# 07_Audio_SPK.net
KiCad netlist of a schematic drawn in Altium Designer
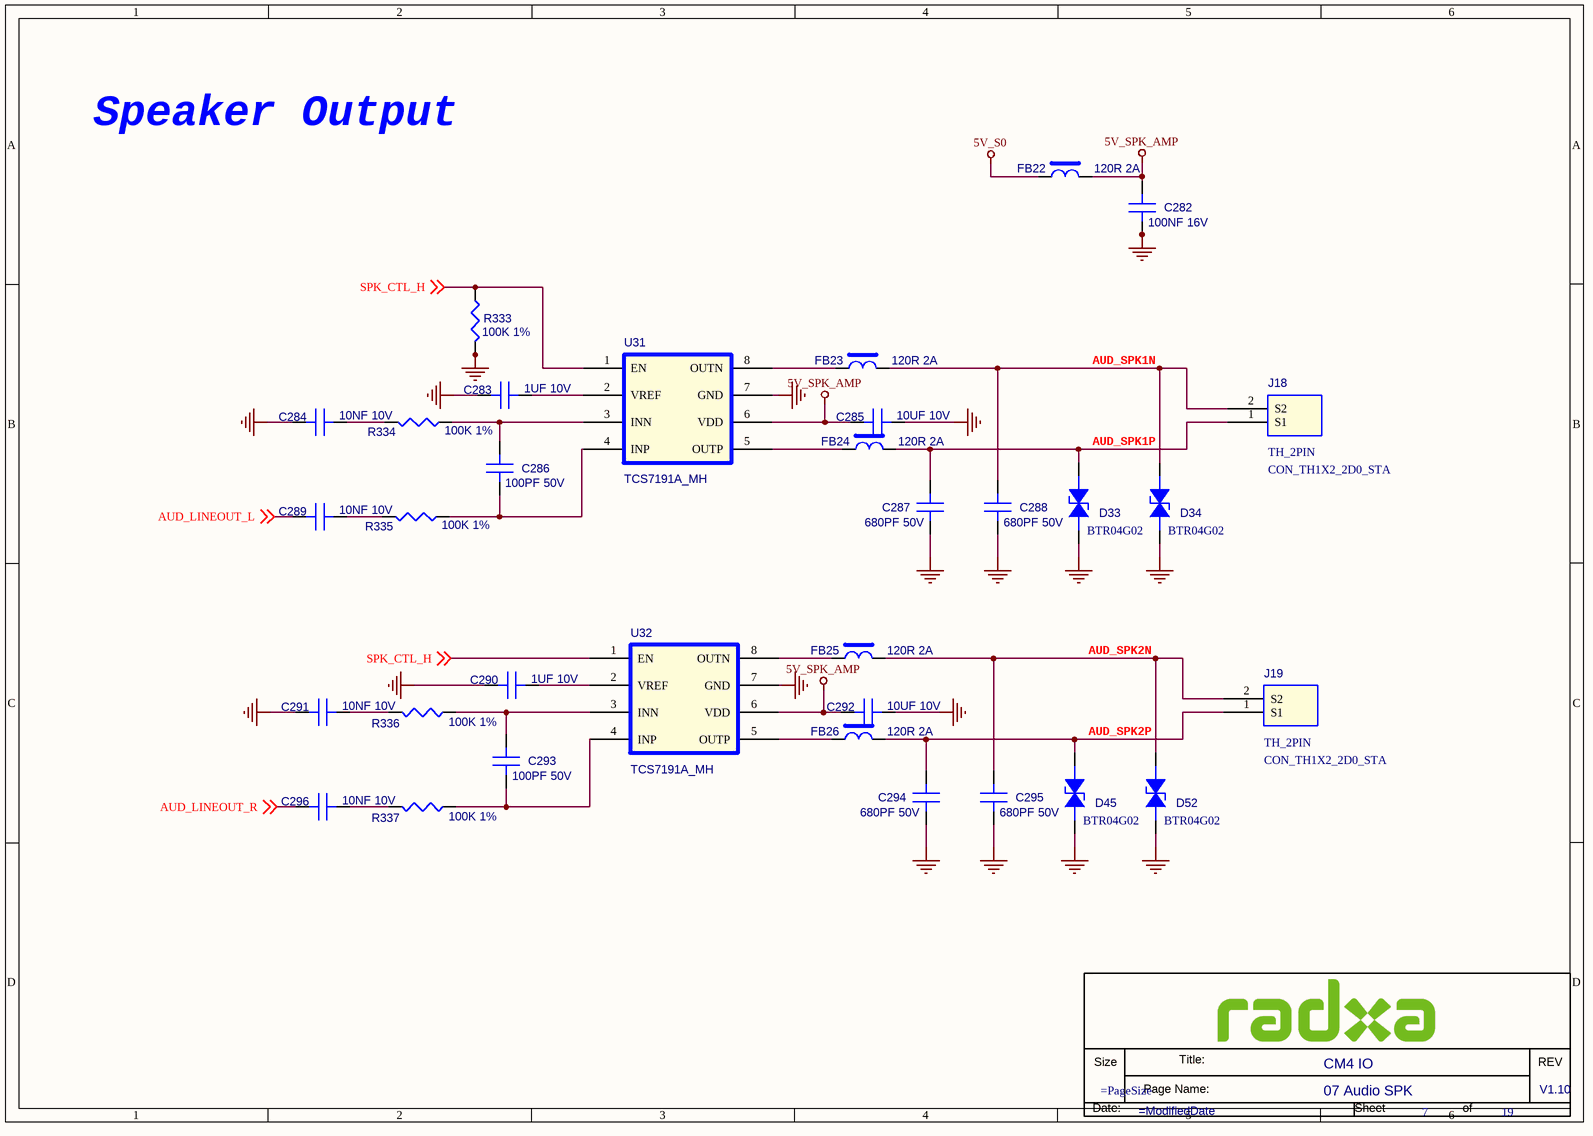
[diagram p0: 07 Audio SPK.SchDoc]

(export (version "E")
  (design (tool "Eeschema 10.0.6"))
  (components
    (comp (ref "C282")
      (value "100NF 16V")
      (footprint "C0201")
      (description "SMD  0201  100NF  16V  X5R  ±20%  ROHS")
      (fields (field (name "PART NUMBER") "A1C01.00099"))
      (libsource (lib "*") (part "C"))
    )
    (comp (ref "C283")
      (value "1UF 10V")
      (footprint "C0201")
      (description "SMD  0201  1UF  10V  X5R  ±20%  ROHS")
      (fields (field (name "PART NUMBER") "A1C01.00081"))
      (libsource (lib "*") (part "C"))
    )
    (comp (ref "C284")
      (value "10NF 10V")
      (footprint "C0201")
      (description "SMD  0201  10NF  10V  X5R  ±20%  ROHS")
      (fields (field (name "PART NUMBER") "A1C01.00095"))
      (libsource (lib "*") (part "C"))
    )
    (comp (ref "C285")
      (value "10UF 10V")
      (footprint "C0603")
      (description "SMD  0603  10UF  10V  X5R  ±20%  ROHS")
      (fields (field (name "PART NUMBER") "A1C01.00075"))
      (libsource (lib "*") (part "C"))
    )
    (comp (ref "C286")
      (value "100PF 50V")
      (footprint "C0201")
      (description "SMD  0201  100PF  50V  NPO  ±5%  ROHS")
      (fields (field (name "PART NUMBER") "A1C01.00382"))
      (libsource (lib "*") (part "C"))
    )
    (comp (ref "C287")
      (value "680PF 50V")
      (footprint "C0201")
      (description "SMD  0201  680PF  50V  X7R  ±10%  ROHS")
      (fields (field (name "PART NUMBER") "A1C01.00071"))
      (libsource (lib "*") (part "C"))
    )
    (comp (ref "C288")
      (value "680PF 50V")
      (footprint "C0201")
      (description "SMD  0201  680PF  50V  X7R  ±10%  ROHS")
      (fields (field (name "PART NUMBER") "A1C01.00071"))
      (libsource (lib "*") (part "C"))
    )
    (comp (ref "C289")
      (value "10NF 10V")
      (footprint "C0201")
      (description "SMD  0201  10NF  10V  X5R  ±20%  ROHS")
      (fields (field (name "PART NUMBER") "A1C01.00095"))
      (libsource (lib "*") (part "C"))
    )
    (comp (ref "C290")
      (value "1UF 10V")
      (footprint "C0201")
      (description "SMD  0201  1UF  10V  X5R  ±20%  ROHS")
      (fields (field (name "PART NUMBER") "A1C01.00081"))
      (libsource (lib "*") (part "C"))
    )
    (comp (ref "C291")
      (value "10NF 10V")
      (footprint "C0201")
      (description "SMD  0201  10NF  10V  X5R  ±20%  ROHS")
      (fields (field (name "PART NUMBER") "A1C01.00095"))
      (libsource (lib "*") (part "C"))
    )
    (comp (ref "C292")
      (value "10UF 10V")
      (footprint "C0603")
      (description "SMD  0603  10UF  10V  X5R  ±20%  ROHS")
      (fields (field (name "PART NUMBER") "A1C01.00075"))
      (libsource (lib "*") (part "C"))
    )
    (comp (ref "C293")
      (value "100PF 50V")
      (footprint "C0201")
      (description "SMD  0201  100PF  50V  NPO  ±5%  ROHS")
      (fields (field (name "PART NUMBER") "A1C01.00382"))
      (libsource (lib "*") (part "C"))
    )
    (comp (ref "C294")
      (value "680PF 50V")
      (footprint "C0201")
      (description "SMD  0201  680PF  50V  X7R  ±10%  ROHS")
      (fields (field (name "PART NUMBER") "A1C01.00071"))
      (libsource (lib "*") (part "C"))
    )
    (comp (ref "C295")
      (value "680PF 50V")
      (footprint "C0201")
      (description "SMD  0201  680PF  50V  X7R  ±10%  ROHS")
      (fields (field (name "PART NUMBER") "A1C01.00071"))
      (libsource (lib "*") (part "C"))
    )
    (comp (ref "C296")
      (value "10NF 10V")
      (footprint "C0201")
      (description "SMD  0201  10NF  10V  X5R  ±20%  ROHS")
      (fields (field (name "PART NUMBER") "A1C01.00095"))
      (libsource (lib "*") (part "C"))
    )
    (comp (ref "D33")
      (value "BTR04G02")
      (footprint "DFN1006-2L")
      (description "SMD  编带  0402  BTR04G02  B-tron  ROHS")
      (fields (field (name "PART NUMBER") "A1D02.00002"))
      (libsource (lib "*") (part "ESD"))
    )
    (comp (ref "D34")
      (value "BTR04G02")
      (footprint "DFN1006-2L")
      (description "SMD  编带  0402  BTR04G02  B-tron  ROHS")
      (fields (field (name "PART NUMBER") "A1D02.00002"))
      (libsource (lib "*") (part "ESD"))
    )
    (comp (ref "D45")
      (value "BTR04G02")
      (footprint "DFN1006-2L")
      (description "SMD  编带  0402  BTR04G02  B-tron  ROHS")
      (fields (field (name "PART NUMBER") "A1D02.00002"))
      (libsource (lib "*") (part "ESD"))
    )
    (comp (ref "D52")
      (value "BTR04G02")
      (footprint "DFN1006-2L")
      (description "SMD  编带  0402  BTR04G02  B-tron  ROHS")
      (fields (field (name "PART NUMBER") "A1D02.00002"))
      (libsource (lib "*") (part "ESD"))
    )
    (comp (ref "FB22")
      (value "120R 2A")
      (footprint "FB0402")
      (description "SMD  0402  FB120R  2A  ±25%  ROHS")
      (fields (field (name "PART NUMBER") "A1L09.00004"))
      (libsource (lib "*") (part "BEAD"))
    )
    (comp (ref "FB23")
      (value "120R 2A")
      (footprint "FB0402")
      (description "SMD  0402  FB120R  2A  ±25%  ROHS")
      (fields (field (name "PART NUMBER") "A1L09.00004"))
      (libsource (lib "*") (part "BEAD"))
    )
    (comp (ref "FB24")
      (value "120R 2A")
      (footprint "FB0402")
      (description "SMD  0402  FB120R  2A  ±25%  ROHS")
      (fields (field (name "PART NUMBER") "A1L09.00004"))
      (libsource (lib "*") (part "BEAD"))
    )
    (comp (ref "FB25")
      (value "120R 2A")
      (footprint "FB0402")
      (description "SMD  0402  FB120R  2A  ±25%  ROHS")
      (fields (field (name "PART NUMBER") "A1L09.00004"))
      (libsource (lib "*") (part "BEAD"))
    )
    (comp (ref "FB26")
      (value "120R 2A")
      (footprint "FB0402")
      (description "SMD  0402  FB120R  2A  ±25%  ROHS")
      (fields (field (name "PART NUMBER") "A1L09.00004"))
      (libsource (lib "*") (part "BEAD"))
    )
    (comp (ref "J18")
      (value "TH_2PIN")
      (footprint "CON_TH1X2_2D54_STA")
      (fields (field (name "PART NUMBER") "A1J02.00089") (field (name "PCB FOOTPRINT") "CON_TH1X2_2D0_STA"))
      (libsource (lib "*") (part "TH_2PIN"))
    )
    (comp (ref "J19")
      (value "TH_2PIN")
      (footprint "CON_TH1X2_2D54_STA")
      (fields (field (name "PART NUMBER") "A1J02.00089") (field (name "PCB FOOTPRINT") "CON_TH1X2_2D0_STA"))
      (libsource (lib "*") (part "TH_2PIN"))
    )
    (comp (ref "R333")
      (value "100K 1%")
      (footprint "R0402")
      (description "SMD  0201  100K  1/20W  ±1%  ROHS")
      (fields (field (name "PART NUMBER") "A1R01.00165"))
      (libsource (lib "*") (part "R"))
    )
    (comp (ref "R334")
      (value "100K 1%")
      (footprint "R0402")
      (description "SMD  0201  100K  1/20W  ±1%  ROHS")
      (fields (field (name "PART NUMBER") "A1R01.00165"))
      (libsource (lib "*") (part "R"))
    )
    (comp (ref "R335")
      (value "100K 1%")
      (footprint "R0402")
      (description "SMD  0201  100K  1/20W  ±1%  ROHS")
      (fields (field (name "PART NUMBER") "A1R01.00165"))
      (libsource (lib "*") (part "R"))
    )
    (comp (ref "R336")
      (value "100K 1%")
      (footprint "R0402")
      (description "SMD  0201  100K  1/20W  ±1%  ROHS")
      (fields (field (name "PART NUMBER") "A1R01.00165"))
      (libsource (lib "*") (part "R"))
    )
    (comp (ref "R337")
      (value "100K 1%")
      (footprint "R0402")
      (description "SMD  0201  100K  1/20W  ±1%  ROHS")
      (fields (field (name "PART NUMBER") "A1R01.00165"))
      (libsource (lib "*") (part "R"))
    )
    (comp (ref "U31")
      (value "TCS7191A_MH")
      (footprint "MSOP8_0D65_5D0")
      (description "SMD  音频功率放大器  TCS7191A_MH  MSOP-8  TCS(汤诚)  ROHS")
      (fields (field (name "PART NUMBER") "A1I01.00891"))
      (libsource (lib "*") (part "TCS7191A_MH"))
    )
    (comp (ref "U32")
      (value "TCS7191A_MH")
      (footprint "MSOP8_0D65_5D0")
      (description "SMD  音频功率放大器  TCS7191A_MH  MSOP-8  TCS(汤诚)  ROHS")
      (fields (field (name "PART NUMBER") "A1I01.00891"))
      (libsource (lib "*") (part "TCS7191A_MH"))
    )
  )
  (nets
    (net (code "1") (name "/AUD_SPK1N") (class "Default")
      (node (ref "C288") (pin "1") (pinfunction "A_1") (pintype "passive"))
      (node (ref "D34") (pin "2") (pinfunction "CATHODE_2") (pintype "passive"))
      (node (ref "FB23") (pin "2") (pinfunction "2_2") (pintype "passive"))
      (node (ref "J18") (pin "2") (pinfunction "S2_2") (pintype "passive"))
    )
    (net (code "2") (name "/AUD_SPK1P") (class "Default")
      (node (ref "C287") (pin "1") (pinfunction "A_1") (pintype "passive"))
      (node (ref "D33") (pin "2") (pinfunction "CATHODE_2") (pintype "passive"))
      (node (ref "FB24") (pin "2") (pinfunction "2_2") (pintype "passive"))
      (node (ref "J18") (pin "1") (pinfunction "S1_1") (pintype "passive"))
    )
    (net (code "3") (name "/AUD_SPK2N") (class "Default")
      (node (ref "C295") (pin "1") (pinfunction "A_1") (pintype "passive"))
      (node (ref "D52") (pin "2") (pinfunction "CATHODE_2") (pintype "passive"))
      (node (ref "FB25") (pin "2") (pinfunction "2_2") (pintype "passive"))
      (node (ref "J19") (pin "2") (pinfunction "S2_2") (pintype "passive"))
    )
    (net (code "4") (name "/AUD_SPK2P") (class "Default")
      (node (ref "C294") (pin "1") (pinfunction "A_1") (pintype "passive"))
      (node (ref "D45") (pin "2") (pinfunction "CATHODE_2") (pintype "passive"))
      (node (ref "FB26") (pin "2") (pinfunction "2_2") (pintype "passive"))
      (node (ref "J19") (pin "1") (pinfunction "S1_1") (pintype "passive"))
    )
    (net (code "5") (name "5V_S0") (class "Default")
      (node (ref "FB22") (pin "1") (pinfunction "1_1") (pintype "passive"))
    )
    (net (code "6") (name "5V_SPK_AMP") (class "Default")
      (node (ref "C282") (pin "1") (pinfunction "A_1") (pintype "passive"))
      (node (ref "C285") (pin "1") (pinfunction "A_1") (pintype "passive"))
      (node (ref "C292") (pin "1") (pinfunction "A_1") (pintype "passive"))
      (node (ref "FB22") (pin "2") (pinfunction "2_2") (pintype "passive"))
      (node (ref "U31") (pin "6") (pinfunction "VDD_6") (pintype "passive"))
      (node (ref "U32") (pin "6") (pinfunction "VDD_6") (pintype "passive"))
    )
    (net (code "7") (name "AUD_LINEOUT_L") (class "Default")
      (node (ref "C289") (pin "1") (pinfunction "A_1") (pintype "passive"))
    )
    (net (code "8") (name "AUD_LINEOUT_R") (class "Default")
      (node (ref "C296") (pin "1") (pinfunction "A_1") (pintype "passive"))
    )
    (net (code "9") (name "GND") (class "Default")
      (node (ref "C282") (pin "2") (pinfunction "B_2") (pintype "passive"))
      (node (ref "C283") (pin "1") (pinfunction "A_1") (pintype "passive"))
      (node (ref "C284") (pin "1") (pinfunction "A_1") (pintype "passive"))
      (node (ref "C285") (pin "2") (pinfunction "B_2") (pintype "passive"))
      (node (ref "C287") (pin "2") (pinfunction "B_2") (pintype "passive"))
      (node (ref "C288") (pin "2") (pinfunction "B_2") (pintype "passive"))
      (node (ref "C290") (pin "1") (pinfunction "A_1") (pintype "passive"))
      (node (ref "C291") (pin "1") (pinfunction "A_1") (pintype "passive"))
      (node (ref "C292") (pin "2") (pinfunction "B_2") (pintype "passive"))
      (node (ref "C294") (pin "2") (pinfunction "B_2") (pintype "passive"))
      (node (ref "C295") (pin "2") (pinfunction "B_2") (pintype "passive"))
      (node (ref "D33") (pin "1") (pinfunction "ANODE_1") (pintype "passive"))
      (node (ref "D34") (pin "1") (pinfunction "ANODE_1") (pintype "passive"))
      (node (ref "D45") (pin "1") (pinfunction "ANODE_1") (pintype "passive"))
      (node (ref "D52") (pin "1") (pinfunction "ANODE_1") (pintype "passive"))
      (node (ref "R333") (pin "2") (pinfunction "2_2") (pintype "passive"))
      (node (ref "U31") (pin "7") (pinfunction "GND_7") (pintype "passive"))
      (node (ref "U32") (pin "7") (pinfunction "GND_7") (pintype "passive"))
    )
    (net (code "10") (name "Net-(C283-B)") (class "Default")
      (node (ref "C283") (pin "2") (pinfunction "B_2") (pintype "passive"))
      (node (ref "U31") (pin "2") (pinfunction "VREF_2") (pintype "passive"))
    )
    (net (code "11") (name "Net-(C284-B)") (class "Default")
      (node (ref "C284") (pin "2") (pinfunction "B_2") (pintype "passive"))
      (node (ref "R334") (pin "1") (pinfunction "1_1") (pintype "passive"))
    )
    (net (code "12") (name "Net-(C286-A)") (class "Default")
      (node (ref "C286") (pin "1") (pinfunction "A_1") (pintype "passive"))
      (node (ref "R334") (pin "2") (pinfunction "2_2") (pintype "passive"))
      (node (ref "U31") (pin "3") (pinfunction "INN_3") (pintype "passive"))
    )
    (net (code "13") (name "Net-(C286-B)") (class "Default")
      (node (ref "C286") (pin "2") (pinfunction "B_2") (pintype "passive"))
      (node (ref "R335") (pin "2") (pinfunction "2_2") (pintype "passive"))
      (node (ref "U31") (pin "4") (pinfunction "INP_4") (pintype "passive"))
    )
    (net (code "14") (name "Net-(C289-B)") (class "Default")
      (node (ref "C289") (pin "2") (pinfunction "B_2") (pintype "passive"))
      (node (ref "R335") (pin "1") (pinfunction "1_1") (pintype "passive"))
    )
    (net (code "15") (name "Net-(C290-B)") (class "Default")
      (node (ref "C290") (pin "2") (pinfunction "B_2") (pintype "passive"))
      (node (ref "U32") (pin "2") (pinfunction "VREF_2") (pintype "passive"))
    )
    (net (code "16") (name "Net-(C291-B)") (class "Default")
      (node (ref "C291") (pin "2") (pinfunction "B_2") (pintype "passive"))
      (node (ref "R336") (pin "1") (pinfunction "1_1") (pintype "passive"))
    )
    (net (code "17") (name "Net-(C293-A)") (class "Default")
      (node (ref "C293") (pin "1") (pinfunction "A_1") (pintype "passive"))
      (node (ref "R336") (pin "2") (pinfunction "2_2") (pintype "passive"))
      (node (ref "U32") (pin "3") (pinfunction "INN_3") (pintype "passive"))
    )
    (net (code "18") (name "Net-(C293-B)") (class "Default")
      (node (ref "C293") (pin "2") (pinfunction "B_2") (pintype "passive"))
      (node (ref "R337") (pin "2") (pinfunction "2_2") (pintype "passive"))
      (node (ref "U32") (pin "4") (pinfunction "INP_4") (pintype "passive"))
    )
    (net (code "19") (name "Net-(C296-B)") (class "Default")
      (node (ref "C296") (pin "2") (pinfunction "B_2") (pintype "passive"))
      (node (ref "R337") (pin "1") (pinfunction "1_1") (pintype "passive"))
    )
    (net (code "20") (name "Net-(U31-OUTN)") (class "Default")
      (node (ref "FB23") (pin "1") (pinfunction "1_1") (pintype "passive"))
      (node (ref "U31") (pin "8") (pinfunction "OUTN_8") (pintype "passive"))
    )
    (net (code "21") (name "Net-(U31-OUTP)") (class "Default")
      (node (ref "FB24") (pin "1") (pinfunction "1_1") (pintype "passive"))
      (node (ref "U31") (pin "5") (pinfunction "OUTP_5") (pintype "passive"))
    )
    (net (code "22") (name "Net-(U32-OUTN)") (class "Default")
      (node (ref "FB25") (pin "1") (pinfunction "1_1") (pintype "passive"))
      (node (ref "U32") (pin "8") (pinfunction "OUTN_8") (pintype "passive"))
    )
    (net (code "23") (name "Net-(U32-OUTP)") (class "Default")
      (node (ref "FB26") (pin "1") (pinfunction "1_1") (pintype "passive"))
      (node (ref "U32") (pin "5") (pinfunction "OUTP_5") (pintype "passive"))
    )
    (net (code "24") (name "SPK_CTL_H") (class "Default")
      (node (ref "R333") (pin "1") (pinfunction "1_1") (pintype "passive"))
      (node (ref "U31") (pin "1") (pinfunction "EN_1") (pintype "passive"))
      (node (ref "U32") (pin "1") (pinfunction "EN_1") (pintype "passive"))
    )
  )
)
